# Sensors.net
KiCad netlist of a schematic drawn in Altium Designer
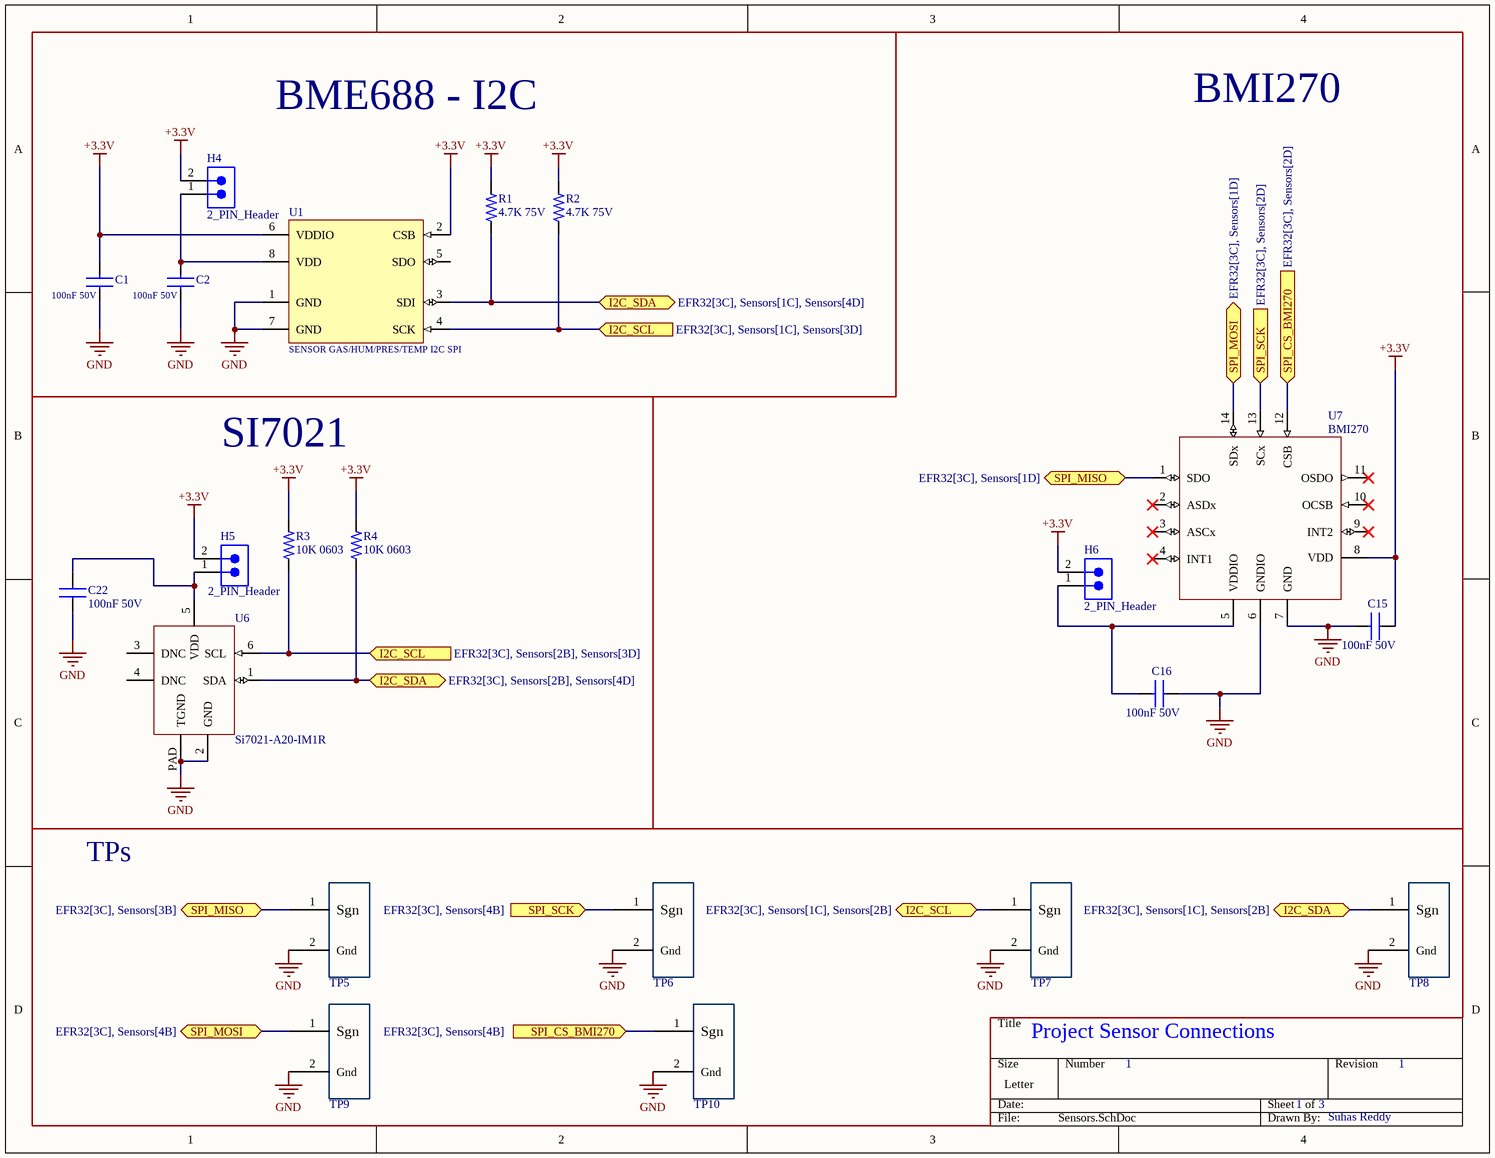
[diagram p0: Sensors.SchDoc]

(export (version "E")
  (design (tool "Eeschema 10.0.6"))
  (components
    (comp (ref "C1")
      (value "100nF 50V")
      (footprint "CAP_0603_1MM")
      (fields
        (field (name "MANUFACTURER") "Yageo")
        (field (name "MANUFACTURER PART NUMBER") "CC0603ZRY5V9BB104")
      )
      (libsource (lib "LPEDT_project_library") (part "CC0603ZRY5V9BB104"))
    )
    (comp (ref "C2")
      (value "100nF 50V")
      (footprint "CAP_0603_1MM")
      (fields
        (field (name "MANUFACTURER") "Yageo")
        (field (name "MANUFACTURER PART NUMBER") "CC0603ZRY5V9BB104")
      )
      (libsource (lib "LPEDT_project_library") (part "CC0603ZRY5V9BB104"))
    )
    (comp (ref "C15")
      (value "100nF 50V")
      (footprint "CAP_0603_1MM")
      (fields
        (field (name "MANUFACTURER") "Yageo")
        (field (name "MANUFACTURER PART NUMBER") "CC0603ZRY5V9BB104")
      )
      (libsource (lib "LPEDT_project_library") (part "CC_0.1uF_0603_ZRY5V9BB104"))
    )
    (comp (ref "C16")
      (value "100nF 50V")
      (footprint "CAP_0603_1MM")
      (fields
        (field (name "MANUFACTURER") "Yageo")
        (field (name "MANUFACTURER PART NUMBER") "CC0603ZRY5V9BB104")
      )
      (libsource (lib "LPEDT_project_library") (part "CC_0.1uF_0603_ZRY5V9BB104"))
    )
    (comp (ref "C22")
      (value "100nF 50V")
      (footprint "CAP_0603_1MM")
      (fields
        (field (name "MANUFACTURER") "Yageo")
        (field (name "MANUFACTURER PART NUMBER") "CC0603ZRY5V9BB104")
      )
      (libsource (lib "LPEDT_project_library") (part "CC_0.1uF_0603_ZRY5V9BB104"))
    )
    (comp (ref "H4")
      (value "2_PIN_Header")
      (footprint "2-PIN_MALE_HEADER_01-IN")
      (description "CONN HEADER VERT 2POS 2.54MM")
      (fields
        (field (name "MANUFACTURER") "Sullins")
        (field (name "MANUFACTURER PART NUMBER") "PRPC002SAAN-RC")
      )
      (libsource (lib "Connectors") (part "PRPC002SAAN-RC"))
    )
    (comp (ref "H5")
      (value "2_PIN_Header")
      (footprint "2-PIN_MALE_HEADER_01-IN")
      (description "CONN HEADER VERT 2POS 2.54MM")
      (fields
        (field (name "MANUFACTURER") "Sullins")
        (field (name "MANUFACTURER PART NUMBER") "PRPC002SAAN-RC")
      )
      (libsource (lib "Connectors") (part "PRPC002SAAN-RC"))
    )
    (comp (ref "H6")
      (value "2_PIN_Header")
      (footprint "2-PIN_MALE_HEADER_01-IN")
      (description "CONN HEADER VERT 2POS 2.54MM")
      (fields
        (field (name "MANUFACTURER") "Sullins")
        (field (name "MANUFACTURER PART NUMBER") "PRPC002SAAN-RC")
      )
      (libsource (lib "Connectors") (part "PRPC002SAAN-RC"))
    )
    (comp (ref "R1")
      (value "4.7K 75V")
      (footprint "RES_0603_1608X06")
      (fields
        (field (name "MANUFACTURER") "Stackpole Electronics")
        (field (name "MANUFACTURER PART NUMBER") "RMCF0603FT4K70")
        (field (name "TOLERANCE") "1%")
      )
      (libsource (lib "LPEDT_project_library") (part "RMCF0603FT4K70"))
    )
    (comp (ref "R2")
      (value "4.7K 75V")
      (footprint "RES_0603_1608X06")
      (fields
        (field (name "MANUFACTURER") "Stackpole Electronics")
        (field (name "MANUFACTURER PART NUMBER") "RMCF0603FT4K70")
        (field (name "TOLERANCE") "1%")
      )
      (libsource (lib "LPEDT_project_library") (part "RMCF0603FT4K70"))
    )
    (comp (ref "R3")
      (value "10K 0603")
      (footprint "RES_0603_1608X06")
      (fields
        (field (name "MANUFACTURER") "Yageo")
        (field (name "MANUFACTURER PART NUMBER") "RC0603FR-0710KL")
        (field (name "TOLERANCE") "1%")
      )
      (libsource (lib "LPEDT_project_library") (part "RC0603FR-0710KL"))
    )
    (comp (ref "R4")
      (value "10K 0603")
      (footprint "RES_0603_1608X06")
      (fields
        (field (name "MANUFACTURER") "Yageo")
        (field (name "MANUFACTURER PART NUMBER") "RC0603FR-0710KL")
        (field (name "TOLERANCE") "1%")
      )
      (libsource (lib "LPEDT_project_library") (part "RC0603FR-0710KL"))
    )
    (comp (ref "TP5")
      (value "TP_Active_Probe")
      (footprint "Active_Probe")
      (description "Active Probe Test Point footprint")
      (libsource (lib "ECEN5730Lib_Manual_2022_07LibPkg_1") (part "TP_Active_Probe"))
    )
    (comp (ref "TP6")
      (value "TP_Active_Probe")
      (footprint "Active_Probe")
      (description "Active Probe Test Point footprint")
      (libsource (lib "ECEN5730Lib_Manual_2022_07LibPkg_1") (part "TP_Active_Probe"))
    )
    (comp (ref "TP7")
      (value "TP_Active_Probe")
      (footprint "Active_Probe")
      (description "Active Probe Test Point footprint")
      (libsource (lib "ECEN5730Lib_Manual_2022_07LibPkg_1") (part "TP_Active_Probe"))
    )
    (comp (ref "TP8")
      (value "TP_Active_Probe")
      (footprint "Active_Probe")
      (description "Active Probe Test Point footprint")
      (libsource (lib "ECEN5730Lib_Manual_2022_07LibPkg_1") (part "TP_Active_Probe"))
    )
    (comp (ref "TP9")
      (value "TP_Active_Probe")
      (footprint "Active_Probe")
      (description "Active Probe Test Point footprint")
      (libsource (lib "ECEN5730Lib_Manual_2022_07LibPkg_1") (part "TP_Active_Probe"))
    )
    (comp (ref "TP10")
      (value "TP_Active_Probe")
      (footprint "Active_Probe")
      (description "Active Probe Test Point footprint")
      (libsource (lib "ECEN5730Lib_Manual_2022_07LibPkg_1") (part "TP_Active_Probe"))
    )
    (comp (ref "U1")
      (value "SENSOR GAS/HUM/PRES/TEMP I2C SPI")
      (footprint "LGA_8_300X300X100")
      (description "Gas, Pressure, Temperature and Humidity Sensor Digital Output 1.8V 8-Pin LGA Reel")
      (fields (field (name "MANUFACTURER") "Bosch Tools") (field (name "MANUFACTURER PART NUMBER") "BME688"))
      (libsource (lib "LPEDT_project_library") (part "BME688"))
    )
    (comp (ref "U6")
      (value "Si7021-A20-IM1R")
      (footprint "6-QFN_3x3_Si7021")
      (description "Serial Switch/Digital Sensor, 14 Bit(s), 0.40Cel, Square, Surface Mount")
      (fields
        (field (name "MANUFACTURER") "Silicon Labs")
        (field (name "MANUFACTURER PART NUMBER") "SI7021-A20-IM1R")
      )
      (libsource (lib "LPEDT_project_library") (part "Si7021-A20-IM1R"))
    )
    (comp (ref "U7")
      (value "BMI270")
      (footprint "14-QFN_3x2.5_BMI270")
      (description "BMI270 Series 3.6 V 685 µA Smart Ultra-low Power Inertial Measurement Unit")
      (fields (field (name "MANUFACTURER") "Bosch Tools"))
      (libsource (lib "LPEDT_project_library") (part "BMI270"))
    )
  )
  (nets
    (net (code "1") (name "+3.3V") (class "Default")
      (node (ref "C1") (pin "1") (pinfunction "1_1") (pintype "passive"))
      (node (ref "C15") (pin "1") (pinfunction "1_1") (pintype "passive"))
      (node (ref "H4") (pin "2") (pinfunction "2_2") (pintype "passive"))
      (node (ref "H5") (pin "2") (pinfunction "2_2") (pintype "passive"))
      (node (ref "H6") (pin "2") (pinfunction "2_2") (pintype "passive"))
      (node (ref "R1") (pin "2") (pinfunction "2_2") (pintype "passive"))
      (node (ref "R2") (pin "2") (pinfunction "2_2") (pintype "passive"))
      (node (ref "R3") (pin "2") (pinfunction "2_2") (pintype "passive"))
      (node (ref "R4") (pin "2") (pinfunction "2_2") (pintype "passive"))
      (node (ref "U1") (pin "2") (pinfunction "CSB_2") (pintype "input"))
      (node (ref "U1") (pin "6") (pinfunction "VDDIO_6") (pintype "power_in"))
      (node (ref "U7") (pin "8") (pinfunction "VDD_8") (pintype "power_in"))
    )
    (net (code "2") (name "/I2C_SCL") (class "Default")
      (node (ref "R2") (pin "1") (pinfunction "1_1") (pintype "passive"))
      (node (ref "R3") (pin "1") (pinfunction "1_1") (pintype "passive"))
      (node (ref "TP7") (pin "1") (pinfunction "Sgn_1") (pintype "passive"))
      (node (ref "U1") (pin "4") (pinfunction "SCK_4") (pintype "input"))
      (node (ref "U6") (pin "6") (pinfunction "SCL_6") (pintype "input"))
    )
    (net (code "3") (name "/I2C_SDA") (class "Default")
      (node (ref "R1") (pin "1") (pinfunction "1_1") (pintype "passive"))
      (node (ref "R4") (pin "1") (pinfunction "1_1") (pintype "passive"))
      (node (ref "TP8") (pin "1") (pinfunction "Sgn_1") (pintype "passive"))
      (node (ref "U1") (pin "3") (pinfunction "SDI_3") (pintype "bidirectional"))
      (node (ref "U6") (pin "1") (pinfunction "SDA_1") (pintype "bidirectional"))
    )
    (net (code "4") (name "/SPI_CS_BMI270") (class "Default")
      (node (ref "TP10") (pin "1") (pinfunction "Sgn_1") (pintype "passive"))
      (node (ref "U7") (pin "12") (pinfunction "CSB_12") (pintype "input"))
    )
    (net (code "5") (name "/SPI_MISO") (class "Default")
      (node (ref "TP5") (pin "1") (pinfunction "Sgn_1") (pintype "passive"))
      (node (ref "U7") (pin "1") (pinfunction "SDO_1") (pintype "bidirectional"))
    )
    (net (code "6") (name "/SPI_MOSI") (class "Default")
      (node (ref "TP9") (pin "1") (pinfunction "Sgn_1") (pintype "passive"))
      (node (ref "U7") (pin "14") (pinfunction "SDx_14") (pintype "bidirectional"))
    )
    (net (code "7") (name "/SPI_SCK") (class "Default")
      (node (ref "TP6") (pin "1") (pinfunction "Sgn_1") (pintype "passive"))
      (node (ref "U7") (pin "13") (pinfunction "SCx_13") (pintype "input"))
    )
    (net (code "8") (name "GND") (class "Default")
      (node (ref "C1") (pin "2") (pinfunction "2_2") (pintype "passive"))
      (node (ref "C15") (pin "2") (pinfunction "2_2") (pintype "passive"))
      (node (ref "C16") (pin "1") (pinfunction "1_1") (pintype "passive"))
      (node (ref "C2") (pin "2") (pinfunction "2_2") (pintype "passive"))
      (node (ref "C22") (pin "2") (pinfunction "2_2") (pintype "passive"))
      (node (ref "TP10") (pin "2") (pinfunction "Gnd_2") (pintype "passive"))
      (node (ref "TP5") (pin "2") (pinfunction "Gnd_2") (pintype "passive"))
      (node (ref "TP6") (pin "2") (pinfunction "Gnd_2") (pintype "passive"))
      (node (ref "TP7") (pin "2") (pinfunction "Gnd_2") (pintype "passive"))
      (node (ref "TP8") (pin "2") (pinfunction "Gnd_2") (pintype "passive"))
      (node (ref "TP9") (pin "2") (pinfunction "Gnd_2") (pintype "passive"))
      (node (ref "U1") (pin "1") (pinfunction "GND_1") (pintype "power_in"))
      (node (ref "U1") (pin "7") (pinfunction "GND_7") (pintype "power_in"))
      (node (ref "U6") (pin "2") (pinfunction "GND_2") (pintype "power_in"))
      (node (ref "U6") (pin "PAD") (pinfunction "TGND_PAD") (pintype "power_in"))
      (node (ref "U7") (pin "6") (pinfunction "GNDIO_6") (pintype "power_in"))
      (node (ref "U7") (pin "7") (pinfunction "GND_7") (pintype "power_in"))
    )
    (net (code "9") (name "Net-(U1-VDD)") (class "Default")
      (node (ref "C2") (pin "1") (pinfunction "1_1") (pintype "passive"))
      (node (ref "H4") (pin "1") (pinfunction "1_1") (pintype "passive"))
      (node (ref "U1") (pin "8") (pinfunction "VDD_8") (pintype "power_in"))
    )
    (net (code "10") (name "Net-(U6-VDD)") (class "Default")
      (node (ref "C22") (pin "1") (pinfunction "1_1") (pintype "passive"))
      (node (ref "H5") (pin "1") (pinfunction "1_1") (pintype "passive"))
      (node (ref "U6") (pin "5") (pinfunction "VDD_5") (pintype "power_in"))
    )
    (net (code "11") (name "Net-(U7-VDDIO)") (class "Default")
      (node (ref "C16") (pin "2") (pinfunction "2_2") (pintype "passive"))
      (node (ref "H6") (pin "1") (pinfunction "1_1") (pintype "passive"))
      (node (ref "U7") (pin "5") (pinfunction "VDDIO_5") (pintype "power_in"))
    )
    (net (code "12") (name "unconnected-(U1-SDO-Pad5)") (class "Default")
      (node (ref "U1") (pin "5") (pinfunction "SDO_5") (pintype "bidirectional"))
    )
    (net (code "13") (name "unconnected-(U6-DNC-Pad3)") (class "Default")
      (node (ref "U6") (pin "3") (pinfunction "DNC_3") (pintype "passive"))
    )
    (net (code "14") (name "unconnected-(U6-DNC-Pad4)") (class "Default")
      (node (ref "U6") (pin "4") (pinfunction "DNC_4") (pintype "passive"))
    )
    (net (code "15") (name "unconnected-(U7-ASCx-Pad3)") (class "Default")
      (node (ref "U7") (pin "3") (pinfunction "ASCx_3") (pintype "bidirectional+no_connect"))
    )
    (net (code "16") (name "unconnected-(U7-ASDx-Pad2)") (class "Default")
      (node (ref "U7") (pin "2") (pinfunction "ASDx_2") (pintype "bidirectional+no_connect"))
    )
    (net (code "17") (name "unconnected-(U7-INT1-Pad4)") (class "Default")
      (node (ref "U7") (pin "4") (pinfunction "INT1_4") (pintype "bidirectional+no_connect"))
    )
    (net (code "18") (name "unconnected-(U7-INT2-Pad9)") (class "Default")
      (node (ref "U7") (pin "9") (pinfunction "INT2_9") (pintype "bidirectional+no_connect"))
    )
    (net (code "19") (name "unconnected-(U7-OCSB-Pad10)") (class "Default")
      (node (ref "U7") (pin "10") (pinfunction "OCSB_10") (pintype "input+no_connect"))
    )
    (net (code "20") (name "unconnected-(U7-OSDO-Pad11)") (class "Default")
      (node (ref "U7") (pin "11") (pinfunction "OSDO_11") (pintype "output+no_connect"))
    )
  )
)
